# Sheet1.net
KiCad netlist of a schematic drawn in Altium Designer
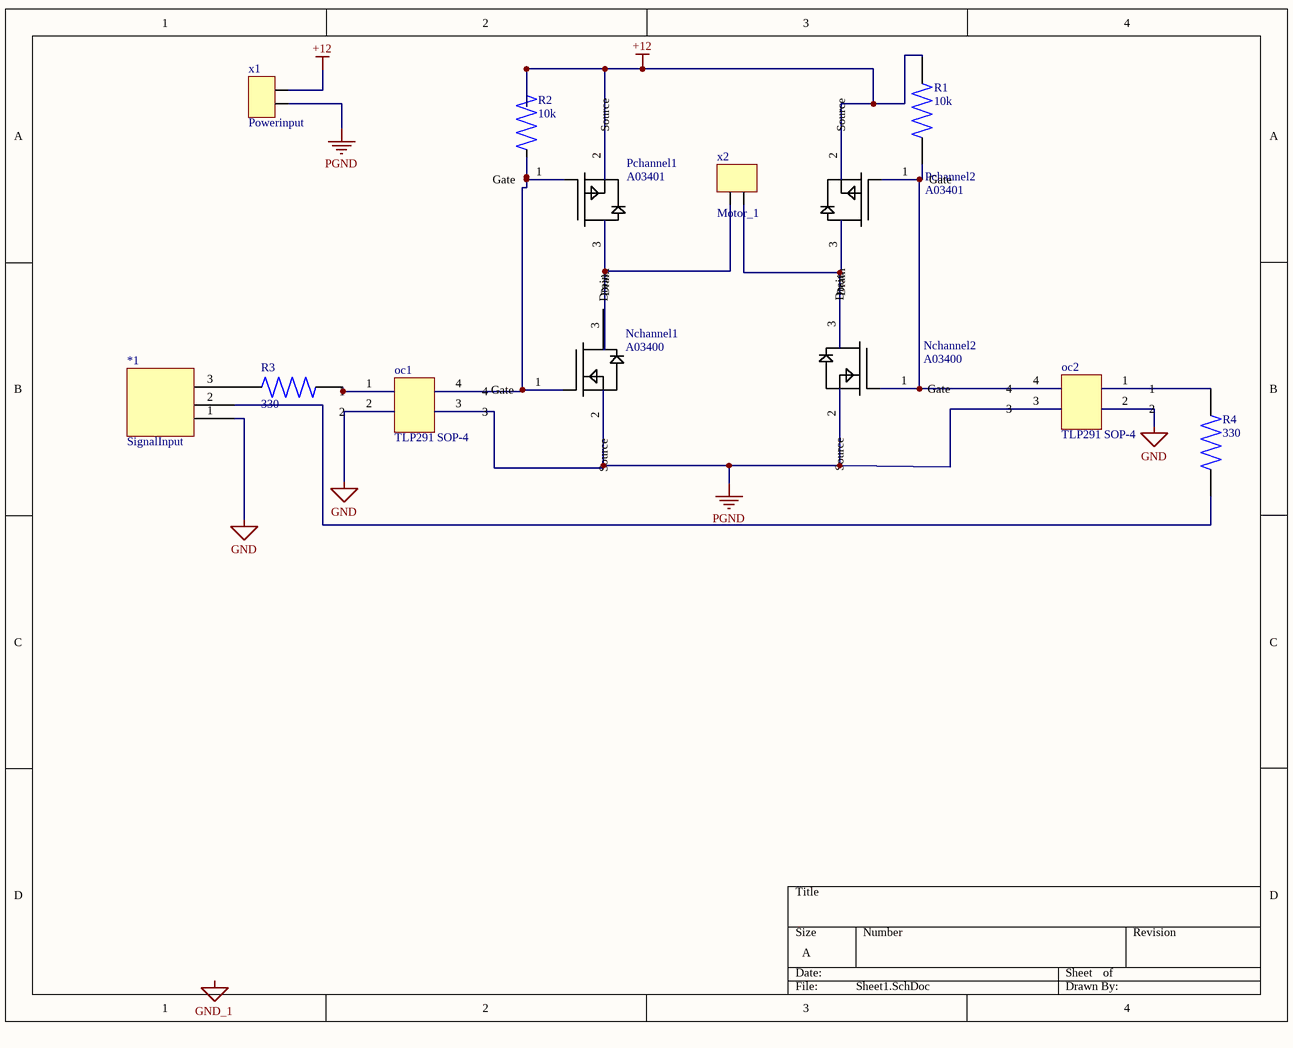
[diagram p0: Sheet1.SchDoc]

(export (version "E")
  (design (tool "Eeschema 10.0.6"))
  (components
    (comp (ref "*1")
      (value "SignalInput")
      (footprint "Terminal block 3")
      (libsource (lib "symbols") (part "Terminal block 3"))
    )
    (comp (ref "Nchannel1") (value "A03400") (footprint "A03400") (libsource (lib "symbols") (part "A03400")))
    (comp (ref "Nchannel2") (value "A03400") (footprint "A03400") (libsource (lib "symbols") (part "A03400")))
    (comp (ref "oc1")
      (value "TLP291 SOP-4")
      (footprint "TLP291 SOP-4")
      (libsource (lib "symbols") (part "TLP291 SOP-4"))
    )
    (comp (ref "oc2")
      (value "TLP291 SOP-4")
      (footprint "TLP291 SOP-4")
      (libsource (lib "") (part "TLP291 SOP-4_1"))
    )
    (comp (ref "Pchannel1") (value "A03401") (footprint "A03401") (libsource (lib "symbols") (part "A03401")))
    (comp (ref "Pchannel2") (value "A03401") (footprint "A03401") (libsource (lib "symbols") (part "A03401")))
    (comp (ref "R1")
      (value "10k")
      (footprint "resss_smd")
      (description "910 Ohms Â±1% 0.125W, 1/8W Chip Resistor 0805 (2012 Metric) Moisture Resistant Thick Film")
      (fields (field (name "MF") "Yageo") (field (name "MP") "RC0805FR-07910RL"))
      (libsource (lib "symbols") (part "resss_smd"))
    )
    (comp (ref "R2")
      (value "10k")
      (footprint "resss_smd")
      (description "910 Ohms Â±1% 0.125W, 1/8W Chip Resistor 0805 (2012 Metric) Moisture Resistant Thick Film")
      (fields (field (name "MF") "Yageo") (field (name "MP") "RC0805FR-07910RL"))
      (libsource (lib "symbols") (part "resss_smd"))
    )
    (comp (ref "R3")
      (value "330")
      (footprint "resss_smd")
      (description "910 Ohms Â±1% 0.125W, 1/8W Chip Resistor 0805 (2012 Metric) Moisture Resistant Thick Film")
      (fields (field (name "MF") "Yageo") (field (name "MP") "RC0805FR-07910RL"))
      (libsource (lib "symbols") (part "resss_smd"))
    )
    (comp (ref "R4")
      (value "330")
      (footprint "resss_smd")
      (description "910 Ohms Â±1% 0.125W, 1/8W Chip Resistor 0805 (2012 Metric) Moisture Resistant Thick Film")
      (fields (field (name "MF") "Yageo") (field (name "MP") "RC0805FR-07910RL"))
      (libsource (lib "symbols") (part "resss_smd"))
    )
    (comp (ref "x1")
      (value "Powerinput")
      (footprint "Terminal Block")
      (libsource (lib "symbols") (part "Terminal Block"))
    )
    (comp (ref "x2")
      (value "Motor_1")
      (footprint "Terminal Block")
      (libsource (lib "") (part "Terminal Block_1"))
    )
  )
  (nets
    (net (code "1") (name "+12") (class "Default")
      (node (ref "Pchannel1") (pin "2") (pinfunction "Source_2") (pintype "passive"))
      (node (ref "Pchannel2") (pin "2") (pinfunction "Source_2") (pintype "passive"))
      (node (ref "R1") (pin "2") (pinfunction "2_2") (pintype "passive"))
      (node (ref "R2") (pin "2") (pinfunction "2_2") (pintype "passive"))
      (node (ref "x1") (pin "2") (pinfunction "2_2") (pintype "passive"))
    )
    (net (code "2") (name "GND") (class "Default")
      (node (ref "*1") (pin "1") (pinfunction "1_1") (pintype "passive"))
      (node (ref "oc1") (pin "2") (pinfunction "2_2") (pintype "passive"))
      (node (ref "oc2") (pin "2") (pinfunction "2_2") (pintype "passive"))
    )
    (net (code "4") (name "Net-(*1-Pad2)") (class "Default")
      (node (ref "*1") (pin "2") (pinfunction "2_2") (pintype "passive"))
      (node (ref "R4") (pin "2") (pinfunction "2_2") (pintype "passive"))
    )
    (net (code "5") (name "Net-(*1-Pad3)") (class "Default")
      (node (ref "*1") (pin "3") (pinfunction "3_3") (pintype "passive"))
      (node (ref "R3") (pin "1") (pinfunction "1_1") (pintype "passive"))
    )
    (net (code "6") (name "Net-(Nchannel1-Drain)") (class "Default")
      (node (ref "Nchannel1") (pin "3") (pinfunction "Drain_3") (pintype "passive"))
      (node (ref "Pchannel1") (pin "3") (pinfunction "Drain_3") (pintype "passive"))
      (node (ref "x2") (pin "1") (pinfunction "1_1") (pintype "passive"))
    )
    (net (code "7") (name "Net-(Nchannel1-Gate)") (class "Default")
      (node (ref "Nchannel1") (pin "1") (pinfunction "Gate_1") (pintype "passive"))
      (node (ref "Pchannel1") (pin "1") (pinfunction "Gate_1") (pintype "passive"))
      (node (ref "R2") (pin "1") (pinfunction "1_1") (pintype "passive"))
      (node (ref "oc1") (pin "4") (pinfunction "4_4") (pintype "passive"))
    )
    (net (code "8") (name "Net-(Nchannel2-Drain)") (class "Default")
      (node (ref "Nchannel2") (pin "3") (pinfunction "Drain_3") (pintype "passive"))
      (node (ref "Pchannel2") (pin "3") (pinfunction "Drain_3") (pintype "passive"))
      (node (ref "x2") (pin "2") (pinfunction "2_2") (pintype "passive"))
    )
    (net (code "9") (name "Net-(Nchannel2-Gate)") (class "Default")
      (node (ref "Nchannel2") (pin "1") (pinfunction "Gate_1") (pintype "passive"))
      (node (ref "Pchannel2") (pin "1") (pinfunction "Gate_1") (pintype "passive"))
      (node (ref "R1") (pin "1") (pinfunction "1_1") (pintype "passive"))
      (node (ref "oc2") (pin "4") (pinfunction "4_4") (pintype "passive"))
    )
    (net (code "10") (name "Net-(R3-Pad2)") (class "Default")
      (node (ref "R3") (pin "2") (pinfunction "2_2") (pintype "passive"))
      (node (ref "oc1") (pin "1") (pinfunction "1_1") (pintype "passive"))
    )
    (net (code "11") (name "Net-(R4-Pad1)") (class "Default")
      (node (ref "R4") (pin "1") (pinfunction "1_1") (pintype "passive"))
      (node (ref "oc2") (pin "1") (pinfunction "1_1") (pintype "passive"))
    )
    (net (code "12") (name "PGND") (class "Default")
      (node (ref "Nchannel1") (pin "2") (pinfunction "Source_2") (pintype "passive"))
      (node (ref "Nchannel2") (pin "2") (pinfunction "Source_2") (pintype "passive"))
      (node (ref "oc1") (pin "3") (pinfunction "3_3") (pintype "passive"))
      (node (ref "oc2") (pin "3") (pinfunction "3_3") (pintype "passive"))
      (node (ref "x1") (pin "1") (pinfunction "1_1") (pintype "passive"))
    )
  )
)
